# Air_Quality_Board.net
KiCad netlist of a schematic drawn in EAGLE
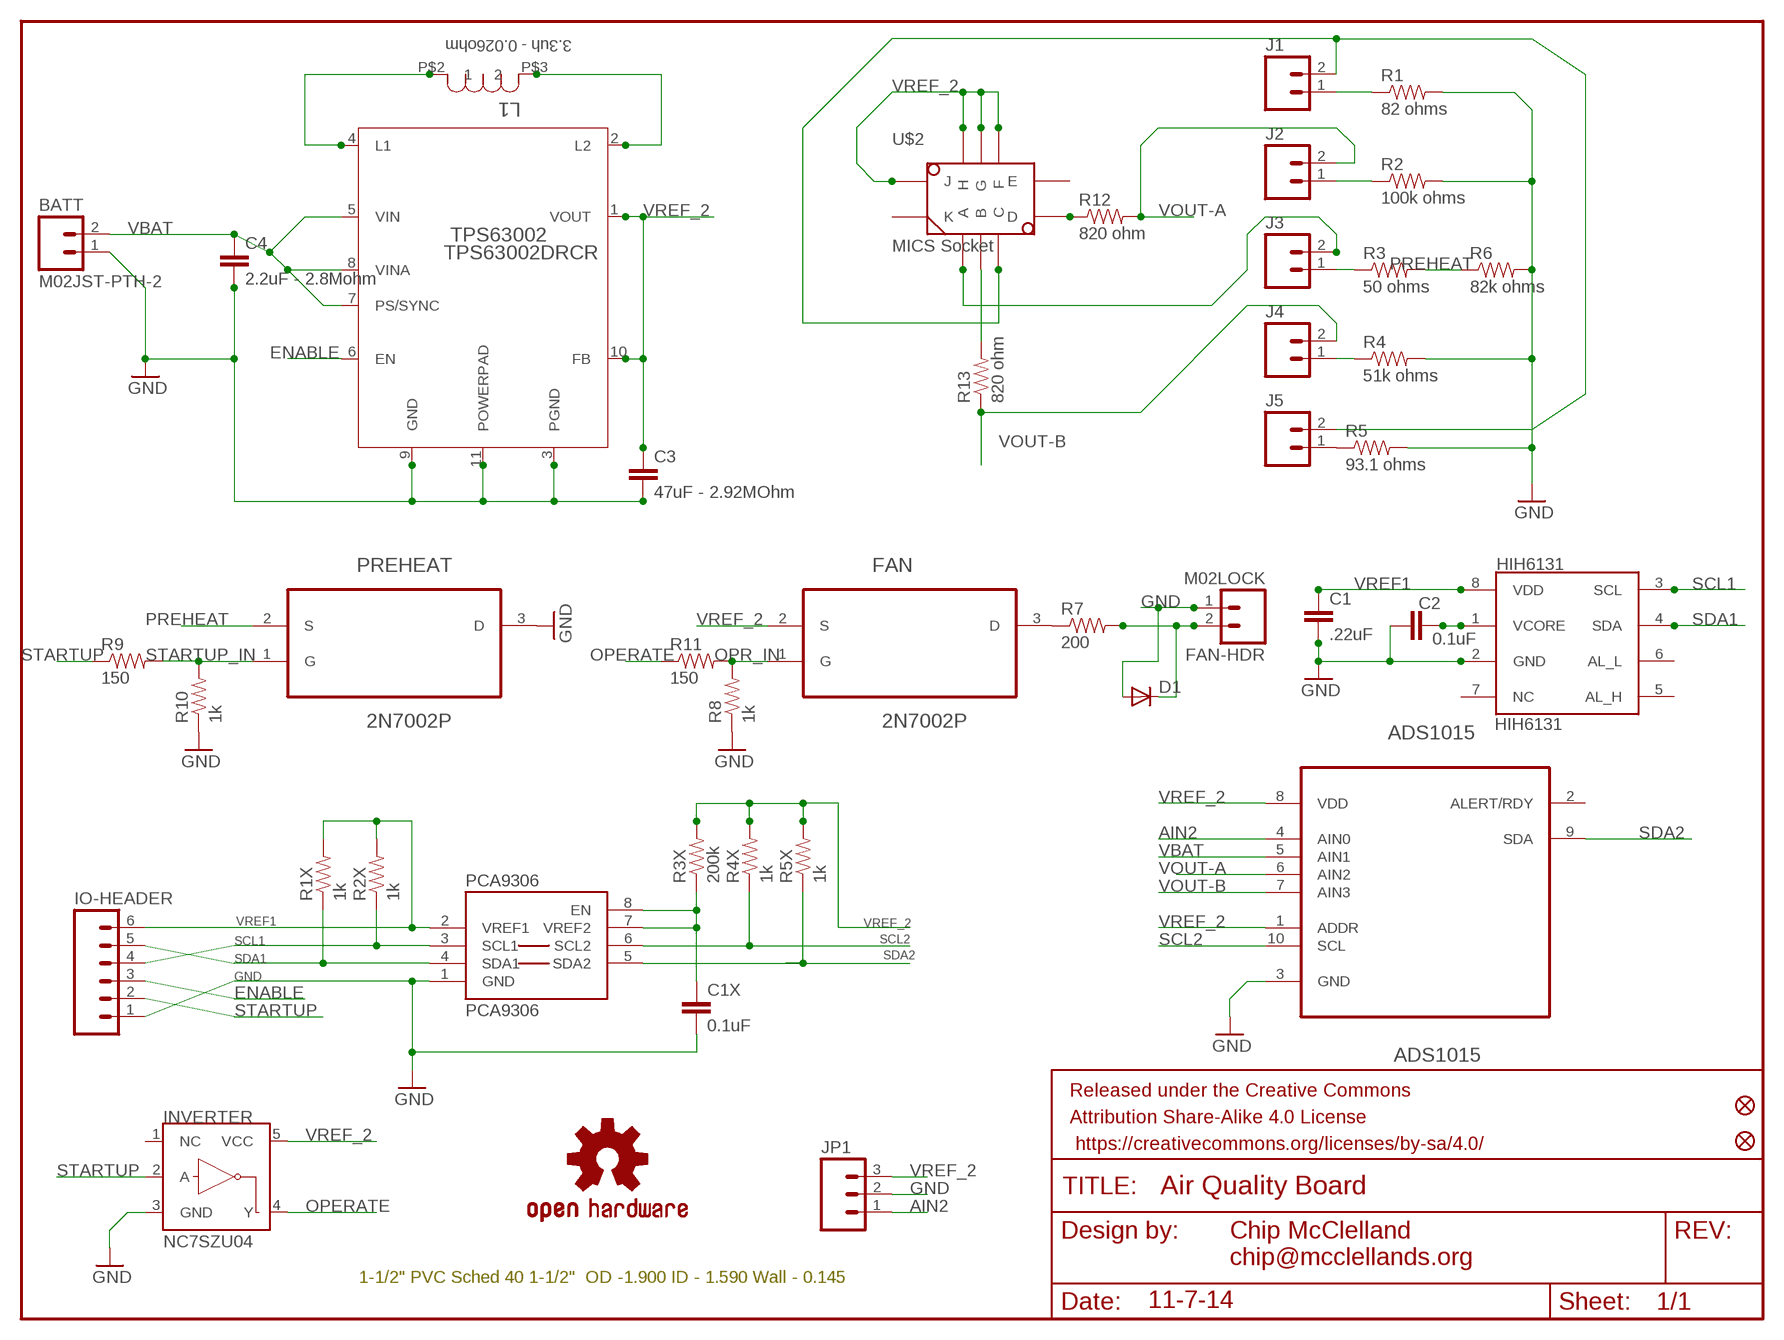
[diagram p0: schematic, sheet 1]

(export (version "E")
  (design (tool "Eeschema 10.0.6"))
  (components
    (comp (ref "ADS1015")
      (value "ADS1015")
      (footprint "eagle-import:SOP50P490X110-10N")
      (fields (field (name "MPN") "ADS1015QDGSRQ1"))
      (libsource (lib "eagle-import") (part "ADS1015QDGSRQ1"))
    )
    (comp (ref "BATT")
      (value "M02JST-PTH-2")
      (footprint "eagle-import:JST-2-PTH")
      (libsource (lib "eagle-import") (part "M02JST-PTH-2"))
    )
    (comp (ref "C1")
      (value ".22uF")
      (footprint "eagle-import:0805")
      (libsource (lib "eagle-import") (part "CAP0805"))
    )
    (comp (ref "C1X")
      (value "0.1uF")
      (footprint "eagle-import:0805")
      (libsource (lib "eagle-import") (part "CAP0805"))
    )
    (comp (ref "C2")
      (value "0.1uF")
      (footprint "eagle-import:0805")
      (libsource (lib "eagle-import") (part "CAP0805"))
    )
    (comp (ref "C3")
      (value "47uF - 2.92MOhm")
      (footprint "eagle-import:0805")
      (libsource (lib "eagle-import") (part "CAP0805"))
    )
    (comp (ref "C4")
      (value "2.2uF - 2.8Mohm")
      (footprint "eagle-import:1206")
      (libsource (lib "eagle-import") (part "CAP1206"))
    )
    (comp (ref "D1")
      (value "DIODESMA")
      (footprint "eagle-import:SMA-DIODE")
      (libsource (lib "eagle-import") (part "DIODESMA"))
    )
    (comp (ref "FAN")
      (value "2N7002P")
      (footprint "eagle-import:SOT95P230X110-3N")
      (libsource (lib "eagle-import") (part "2N7002P"))
    )
    (comp (ref "FAN-HDR")
      (value "M02LOCK")
      (footprint "eagle-import:1X02_LOCK")
      (libsource (lib "eagle-import") (part "M02LOCK"))
    )
    (comp (ref "FRAME1")
      (value "FRAME-LETTER")
      (footprint "eagle-import:CREATIVE_COMMONS")
      (libsource (lib "eagle-import") (part "FRAME-LETTER"))
    )
    (comp (ref "HIH6131")
      (value "HIH6131")
      (footprint "eagle-import:SOIC8")
      (libsource (lib "eagle-import") (part "HIH6131"))
    )
    (comp (ref "IO-HEADER")
      (value "M06LOCK")
      (footprint "eagle-import:1X06_LOCK")
      (libsource (lib "eagle-import") (part "M06LOCK"))
    )
    (comp (ref "J1")
      (value "M02LOCK")
      (footprint "eagle-import:1X02_LOCK")
      (libsource (lib "eagle-import") (part "M02LOCK"))
    )
    (comp (ref "J2")
      (value "M02LOCK")
      (footprint "eagle-import:1X02_LOCK")
      (libsource (lib "eagle-import") (part "M02LOCK"))
    )
    (comp (ref "J3")
      (value "M02LOCK")
      (footprint "eagle-import:1X02_LOCK")
      (libsource (lib "eagle-import") (part "M02LOCK"))
    )
    (comp (ref "J4")
      (value "M02LOCK")
      (footprint "eagle-import:1X02_LOCK")
      (libsource (lib "eagle-import") (part "M02LOCK"))
    )
    (comp (ref "J5")
      (value "M02LOCK")
      (footprint "eagle-import:1X02_LOCK")
      (libsource (lib "eagle-import") (part "M02LOCK"))
    )
    (comp (ref "JP1")
      (value "M03LOCK")
      (footprint "eagle-import:1X03_LOCK")
      (libsource (lib "eagle-import") (part "M03LOCK"))
    )
    (comp (ref "JP7")
      (value "FIDUCIAL1X2.5")
      (footprint "eagle-import:FIDUCIAL-1X2.5")
      (libsource (lib "eagle-import") (part "FIDUCIAL1X2.5"))
    )
    (comp (ref "JP8")
      (value "FIDUCIAL1X2.5")
      (footprint "eagle-import:FIDUCIAL-1X2.5")
      (libsource (lib "eagle-import") (part "FIDUCIAL1X2.5"))
    )
    (comp (ref "L1")
      (value "3.3uh - 0.026ohm")
      (footprint "eagle-import:POWERINDUCTOR")
      (libsource (lib "eagle-import") (part "SRR4028"))
    )
    (comp (ref "LOGO1")
      (value "OSHW-LOGOS")
      (footprint "eagle-import:OSHW-LOGO-S")
      (libsource (lib "eagle-import") (part "OSHW-LOGOS"))
    )
    (comp (ref "NC7SZU04")
      (value "INVERTER")
      (footprint "eagle-import:SOT23-5")
      (libsource (lib "eagle-import") (part "INVERTER"))
    )
    (comp (ref "PCA9306")
      (value "PCA9306")
      (footprint "eagle-import:SOIC8")
      (libsource (lib "eagle-import") (part "PCA9306"))
    )
    (comp (ref "PREHEAT")
      (value "2N7002P")
      (footprint "eagle-import:SOT95P230X110-3N")
      (libsource (lib "eagle-import") (part "2N7002P"))
    )
    (comp (ref "R1")
      (value "82 ohms")
      (footprint "eagle-import:0805")
      (libsource (lib "eagle-import") (part "RESISTOR0805-RES"))
    )
    (comp (ref "R1X")
      (value "1k")
      (footprint "eagle-import:0805")
      (libsource (lib "eagle-import") (part "RESISTOR0805-RES"))
    )
    (comp (ref "R2")
      (value "100k ohms")
      (footprint "eagle-import:0805")
      (libsource (lib "eagle-import") (part "RESISTOR0805-RES"))
    )
    (comp (ref "R2X")
      (value "1k")
      (footprint "eagle-import:0805")
      (libsource (lib "eagle-import") (part "RESISTOR0805-RES"))
    )
    (comp (ref "R3")
      (value "50 ohms")
      (footprint "eagle-import:0805")
      (libsource (lib "eagle-import") (part "RESISTOR0805-RES"))
    )
    (comp (ref "R3X")
      (value "200k")
      (footprint "eagle-import:0805")
      (libsource (lib "eagle-import") (part "RESISTOR0805-RES"))
    )
    (comp (ref "R4")
      (value "51k ohms")
      (footprint "eagle-import:0805")
      (libsource (lib "eagle-import") (part "RESISTOR0805-RES"))
    )
    (comp (ref "R4X")
      (value "1k")
      (footprint "eagle-import:0805")
      (libsource (lib "eagle-import") (part "RESISTOR0805-RES"))
    )
    (comp (ref "R5")
      (value "93.1 ohms")
      (footprint "eagle-import:0805")
      (libsource (lib "eagle-import") (part "RESISTOR0805-RES"))
    )
    (comp (ref "R5X")
      (value "1k")
      (footprint "eagle-import:0805")
      (libsource (lib "eagle-import") (part "RESISTOR0805-RES"))
    )
    (comp (ref "R6")
      (value "82k ohms")
      (footprint "eagle-import:0805")
      (libsource (lib "eagle-import") (part "RESISTOR0805-RES"))
    )
    (comp (ref "R7")
      (value "200")
      (footprint "eagle-import:0805")
      (libsource (lib "eagle-import") (part "RESISTOR0805-RES"))
    )
    (comp (ref "R8")
      (value "1k")
      (footprint "eagle-import:0805")
      (libsource (lib "eagle-import") (part "RESISTOR0805-RES"))
    )
    (comp (ref "R9")
      (value "150")
      (footprint "eagle-import:0805")
      (libsource (lib "eagle-import") (part "RESISTOR0805-RES"))
    )
    (comp (ref "R10")
      (value "1k")
      (footprint "eagle-import:0805")
      (libsource (lib "eagle-import") (part "RESISTOR0805-RES"))
    )
    (comp (ref "R11")
      (value "150")
      (footprint "eagle-import:0805")
      (libsource (lib "eagle-import") (part "RESISTOR0805-RES"))
    )
    (comp (ref "R12")
      (value "820 ohm")
      (footprint "eagle-import:0805")
      (libsource (lib "eagle-import") (part "RESISTOR0805-RES"))
    )
    (comp (ref "R13")
      (value "820 ohm")
      (footprint "eagle-import:0805")
      (libsource (lib "eagle-import") (part "RESISTOR0805-RES"))
    )
    (comp (ref "TPS63002")
      (value "TPS63002DRCR")
      (footprint "eagle-import:NEW-S-PVSON-N10")
      (libsource (lib "eagle-import") (part "TPS63002DRCR"))
    )
    (comp (ref "U$2")
      (value "MICS Socket")
      (footprint "eagle-import:MICS-SMD-SOCKET")
      (libsource (lib "eagle-import") (part "MICS-SMD-SOCKET"))
    )
  )
  (nets
    (net (code "1") (name "/AIN2") (class "Default")
      (node (ref "ADS1015") (pin "4") (pinfunction "AIN0_4") (pintype "input"))
      (node (ref "JP1") (pin "1") (pinfunction "1_1") (pintype "passive"))
    )
    (net (code "2") (name "/ENABLE") (class "Default")
      (node (ref "IO-HEADER") (pin "3") (pinfunction "3_3") (pintype "passive"))
      (node (ref "TPS63002") (pin "6") (pinfunction "EN_6") (pintype "passive"))
    )
    (net (code "3") (name "/OPERATE") (class "Default")
      (node (ref "NC7SZU04") (pin "4") (pinfunction "Y_4") (pintype "bidirectional"))
      (node (ref "R11") (pin "1") (pinfunction "1_1") (pintype "passive"))
    )
    (net (code "4") (name "/OPR_IN") (class "Default")
      (node (ref "FAN") (pin "1") (pinfunction "G_1") (pintype "passive"))
      (node (ref "R11") (pin "2") (pinfunction "2_2") (pintype "passive"))
      (node (ref "R8") (pin "2") (pinfunction "2_2") (pintype "passive"))
    )
    (net (code "5") (name "/PREHEAT") (class "Default")
      (node (ref "PREHEAT") (pin "2") (pinfunction "S_2") (pintype "passive"))
      (node (ref "R3") (pin "2") (pinfunction "2_2") (pintype "passive"))
      (node (ref "R6") (pin "1") (pinfunction "1_1") (pintype "passive"))
    )
    (net (code "6") (name "/SCL1") (class "Default")
      (node (ref "HIH6131") (pin "3") (pinfunction "SCL_3") (pintype "bidirectional"))
      (node (ref "IO-HEADER") (pin "4") (pinfunction "4_4") (pintype "passive"))
      (node (ref "PCA9306") (pin "3") (pinfunction "SCL1_3") (pintype "bidirectional"))
      (node (ref "R2X") (pin "1") (pinfunction "1_1") (pintype "passive"))
    )
    (net (code "7") (name "/SCL2") (class "Default")
      (node (ref "ADS1015") (pin "10") (pinfunction "SCL_10") (pintype "input"))
      (node (ref "PCA9306") (pin "6") (pinfunction "SCL2_6") (pintype "bidirectional"))
      (node (ref "R4X") (pin "1") (pinfunction "1_1") (pintype "passive"))
    )
    (net (code "8") (name "/SDA1") (class "Default")
      (node (ref "HIH6131") (pin "4") (pinfunction "SDA_4") (pintype "bidirectional"))
      (node (ref "IO-HEADER") (pin "5") (pinfunction "5_5") (pintype "passive"))
      (node (ref "PCA9306") (pin "4") (pinfunction "SDA1_4") (pintype "bidirectional"))
      (node (ref "R1X") (pin "1") (pinfunction "1_1") (pintype "passive"))
    )
    (net (code "9") (name "/SDA2") (class "Default")
      (node (ref "ADS1015") (pin "9") (pinfunction "SDA_9") (pintype "bidirectional"))
      (node (ref "PCA9306") (pin "5") (pinfunction "SDA2_5") (pintype "bidirectional"))
      (node (ref "R5X") (pin "1") (pinfunction "1_1") (pintype "passive"))
    )
    (net (code "10") (name "/STARTUP") (class "Default")
      (node (ref "IO-HEADER") (pin "2") (pinfunction "2_2") (pintype "passive"))
      (node (ref "NC7SZU04") (pin "2") (pinfunction "A_2") (pintype "bidirectional"))
      (node (ref "R9") (pin "1") (pinfunction "1_1") (pintype "passive"))
    )
    (net (code "11") (name "/STARTUP_IN") (class "Default")
      (node (ref "PREHEAT") (pin "1") (pinfunction "G_1") (pintype "passive"))
      (node (ref "R10") (pin "2") (pinfunction "2_2") (pintype "passive"))
      (node (ref "R9") (pin "2") (pinfunction "2_2") (pintype "passive"))
    )
    (net (code "12") (name "/VBAT") (class "Default")
      (node (ref "ADS1015") (pin "5") (pinfunction "AIN1_5") (pintype "input"))
      (node (ref "BATT") (pin "2") (pinfunction "2_2") (pintype "passive"))
      (node (ref "C4") (pin "1") (pinfunction "1_1") (pintype "passive"))
      (node (ref "TPS63002") (pin "5") (pinfunction "VIN_5") (pintype "passive"))
      (node (ref "TPS63002") (pin "7") (pinfunction "PS/SYNC_7") (pintype "passive"))
      (node (ref "TPS63002") (pin "8") (pinfunction "VINA_8") (pintype "passive"))
    )
    (net (code "13") (name "/VOUT-A") (class "Default")
      (node (ref "ADS1015") (pin "6") (pinfunction "AIN2_6") (pintype "input"))
      (node (ref "J2") (pin "2") (pinfunction "2_2") (pintype "passive"))
      (node (ref "R12") (pin "2") (pinfunction "2_2") (pintype "passive"))
    )
    (net (code "14") (name "/VOUT-B") (class "Default")
      (node (ref "ADS1015") (pin "7") (pinfunction "AIN3_7") (pintype "input"))
      (node (ref "J4") (pin "2") (pinfunction "2_2") (pintype "passive"))
      (node (ref "R13") (pin "1") (pinfunction "1_1") (pintype "passive"))
    )
    (net (code "15") (name "/VREF1") (class "Default")
      (node (ref "C1") (pin "1") (pinfunction "1_1") (pintype "passive"))
      (node (ref "HIH6131") (pin "8") (pinfunction "VDD_8") (pintype "bidirectional"))
      (node (ref "IO-HEADER") (pin "6") (pinfunction "6_6") (pintype "passive"))
      (node (ref "PCA9306") (pin "2") (pinfunction "VREF1_2") (pintype "bidirectional"))
      (node (ref "R1X") (pin "2") (pinfunction "2_2") (pintype "passive"))
      (node (ref "R2X") (pin "2") (pinfunction "2_2") (pintype "passive"))
    )
    (net (code "16") (name "/VREF_2") (class "Default")
      (node (ref "ADS1015") (pin "1") (pinfunction "ADDR_1") (pintype "input"))
      (node (ref "ADS1015") (pin "8") (pinfunction "VDD_8") (pintype "power_in"))
      (node (ref "C3") (pin "1") (pinfunction "1_1") (pintype "passive"))
      (node (ref "FAN") (pin "2") (pinfunction "S_2") (pintype "passive"))
      (node (ref "JP1") (pin "3") (pinfunction "3_3") (pintype "passive"))
      (node (ref "NC7SZU04") (pin "5") (pinfunction "VCC_5") (pintype "bidirectional"))
      (node (ref "R3X") (pin "2") (pinfunction "2_2") (pintype "passive"))
      (node (ref "R4X") (pin "2") (pinfunction "2_2") (pintype "passive"))
      (node (ref "R5X") (pin "2") (pinfunction "2_2") (pintype "passive"))
      (node (ref "TPS63002") (pin "1") (pinfunction "VOUT_1") (pintype "passive"))
      (node (ref "TPS63002") (pin "10") (pinfunction "FB_10") (pintype "passive"))
      (node (ref "U$2") (pin "F") (pinfunction "F_F") (pintype "bidirectional"))
      (node (ref "U$2") (pin "G") (pinfunction "G_G") (pintype "bidirectional"))
      (node (ref "U$2") (pin "H") (pinfunction "H_H") (pintype "bidirectional"))
      (node (ref "U$2") (pin "J") (pinfunction "J_J") (pintype "bidirectional"))
    )
    (net (code "17") (name "GND") (class "Default")
      (node (ref "ADS1015") (pin "3") (pinfunction "GND_3") (pintype "passive"))
      (node (ref "BATT") (pin "1") (pinfunction "1_1") (pintype "passive"))
      (node (ref "C1") (pin "2") (pinfunction "2_2") (pintype "passive"))
      (node (ref "C1X") (pin "2") (pinfunction "2_2") (pintype "passive"))
      (node (ref "C2") (pin "1") (pinfunction "1_1") (pintype "passive"))
      (node (ref "C3") (pin "2") (pinfunction "2_2") (pintype "passive"))
      (node (ref "C4") (pin "2") (pinfunction "2_2") (pintype "passive"))
      (node (ref "D1") (pin "A") (pinfunction "A_A") (pintype "passive"))
      (node (ref "FAN-HDR") (pin "1") (pinfunction "1_1") (pintype "passive"))
      (node (ref "HIH6131") (pin "2") (pinfunction "GND_2") (pintype "bidirectional"))
      (node (ref "IO-HEADER") (pin "1") (pinfunction "1_1") (pintype "passive"))
      (node (ref "JP1") (pin "2") (pinfunction "2_2") (pintype "passive"))
      (node (ref "NC7SZU04") (pin "3") (pinfunction "GND_3") (pintype "bidirectional"))
      (node (ref "PCA9306") (pin "1") (pinfunction "GND_1") (pintype "bidirectional"))
      (node (ref "PREHEAT") (pin "3") (pinfunction "D_3") (pintype "passive"))
      (node (ref "R1") (pin "2") (pinfunction "2_2") (pintype "passive"))
      (node (ref "R10") (pin "1") (pinfunction "1_1") (pintype "passive"))
      (node (ref "R2") (pin "2") (pinfunction "2_2") (pintype "passive"))
      (node (ref "R4") (pin "2") (pinfunction "2_2") (pintype "passive"))
      (node (ref "R5") (pin "2") (pinfunction "2_2") (pintype "passive"))
      (node (ref "R6") (pin "2") (pinfunction "2_2") (pintype "passive"))
      (node (ref "R8") (pin "1") (pinfunction "1_1") (pintype "passive"))
      (node (ref "TPS63002") (pin "11") (pinfunction "POWERPAD_11") (pintype "passive"))
      (node (ref "TPS63002") (pin "3") (pinfunction "PGND_3") (pintype "passive"))
      (node (ref "TPS63002") (pin "9") (pinfunction "GND_9") (pintype "passive"))
    )
    (net (code "18") (name "Net-(D1-PadC)") (class "Default")
      (node (ref "D1") (pin "C") (pinfunction "C_C") (pintype "passive"))
      (node (ref "FAN-HDR") (pin "2") (pinfunction "2_2") (pintype "passive"))
      (node (ref "R7") (pin "2") (pinfunction "2_2") (pintype "passive"))
    )
    (net (code "19") (name "Net-(FAN-D)") (class "Default")
      (node (ref "FAN") (pin "3") (pinfunction "D_3") (pintype "passive"))
      (node (ref "R7") (pin "1") (pinfunction "1_1") (pintype "passive"))
    )
    (net (code "20") (name "Net-(HIH6131-VCORE)") (class "Default")
      (node (ref "C2") (pin "2") (pinfunction "2_2") (pintype "passive"))
      (node (ref "HIH6131") (pin "1") (pinfunction "VCORE_1") (pintype "bidirectional"))
    )
    (net (code "21") (name "Net-(J1-Pad1)") (class "Default")
      (node (ref "J1") (pin "1") (pinfunction "1_1") (pintype "passive"))
      (node (ref "R1") (pin "1") (pinfunction "1_1") (pintype "passive"))
    )
    (net (code "22") (name "Net-(J1-Pad2)") (class "Default")
      (node (ref "J1") (pin "2") (pinfunction "2_2") (pintype "passive"))
      (node (ref "J5") (pin "2") (pinfunction "2_2") (pintype "passive"))
      (node (ref "U$2") (pin "C") (pinfunction "C_C") (pintype "bidirectional"))
    )
    (net (code "23") (name "Net-(J2-Pad1)") (class "Default")
      (node (ref "J2") (pin "1") (pinfunction "1_1") (pintype "passive"))
      (node (ref "R2") (pin "1") (pinfunction "1_1") (pintype "passive"))
    )
    (net (code "24") (name "Net-(J3-Pad1)") (class "Default")
      (node (ref "J3") (pin "1") (pinfunction "1_1") (pintype "passive"))
      (node (ref "R3") (pin "1") (pinfunction "1_1") (pintype "passive"))
    )
    (net (code "25") (name "Net-(J3-Pad2)") (class "Default")
      (node (ref "J3") (pin "2") (pinfunction "2_2") (pintype "passive"))
      (node (ref "U$2") (pin "A") (pinfunction "A_A") (pintype "bidirectional"))
    )
    (net (code "26") (name "Net-(J4-Pad1)") (class "Default")
      (node (ref "J4") (pin "1") (pinfunction "1_1") (pintype "passive"))
      (node (ref "R4") (pin "1") (pinfunction "1_1") (pintype "passive"))
    )
    (net (code "27") (name "Net-(J5-Pad1)") (class "Default")
      (node (ref "J5") (pin "1") (pinfunction "1_1") (pintype "passive"))
      (node (ref "R5") (pin "1") (pinfunction "1_1") (pintype "passive"))
    )
    (net (code "28") (name "Net-(L1-1)") (class "Default")
      (node (ref "L1") (pin "P$2") (pinfunction "1_P$2") (pintype "passive"))
      (node (ref "TPS63002") (pin "4") (pinfunction "L1_4") (pintype "passive"))
    )
    (net (code "29") (name "Net-(L1-2)") (class "Default")
      (node (ref "L1") (pin "P$3") (pinfunction "2_P$3") (pintype "passive"))
      (node (ref "TPS63002") (pin "2") (pinfunction "L2_2") (pintype "passive"))
    )
    (net (code "30") (name "Net-(PCA9306-EN)") (class "Default")
      (node (ref "C1X") (pin "1") (pinfunction "1_1") (pintype "passive"))
      (node (ref "PCA9306") (pin "7") (pinfunction "VREF2_7") (pintype "bidirectional"))
      (node (ref "PCA9306") (pin "8") (pinfunction "EN_8") (pintype "bidirectional"))
      (node (ref "R3X") (pin "1") (pinfunction "1_1") (pintype "passive"))
    )
    (net (code "31") (name "Net-(R12-Pad1)") (class "Default")
      (node (ref "R12") (pin "1") (pinfunction "1_1") (pintype "passive"))
      (node (ref "U$2") (pin "D") (pinfunction "D_D") (pintype "bidirectional"))
    )
    (net (code "32") (name "Net-(R13-Pad2)") (class "Default")
      (node (ref "R13") (pin "2") (pinfunction "2_2") (pintype "passive"))
      (node (ref "U$2") (pin "B") (pinfunction "B_B") (pintype "bidirectional"))
    )
    (net (code "33") (name "unconnected-(ADS1015-ALERT{slash}RDY-Pad2)") (class "Default")
      (node (ref "ADS1015") (pin "2") (pinfunction "ALERT/RDY_2") (pintype "output"))
    )
    (net (code "34") (name "unconnected-(HIH6131-AL_H-Pad5)") (class "Default")
      (node (ref "HIH6131") (pin "5") (pinfunction "AL_H_5") (pintype "bidirectional"))
    )
    (net (code "35") (name "unconnected-(HIH6131-AL_L-Pad6)") (class "Default")
      (node (ref "HIH6131") (pin "6") (pinfunction "AL_L_6") (pintype "bidirectional"))
    )
    (net (code "36") (name "unconnected-(HIH6131-NC-Pad7)") (class "Default")
      (node (ref "HIH6131") (pin "7") (pinfunction "NC_7") (pintype "bidirectional"))
    )
    (net (code "37") (name "unconnected-(NC7SZU04-NC-Pad1)") (class "Default")
      (node (ref "NC7SZU04") (pin "1") (pinfunction "NC_1") (pintype "bidirectional"))
    )
    (net (code "38") (name "unconnected-(U$2-PadE)") (class "Default")
      (node (ref "U$2") (pin "E") (pinfunction "E_E") (pintype "bidirectional"))
    )
    (net (code "39") (name "unconnected-(U$2-PadK)") (class "Default")
      (node (ref "U$2") (pin "K") (pinfunction "K_K") (pintype "bidirectional"))
    )
  )
)
